# icsp.net
KiCad netlist of a schematic drawn in EAGLE
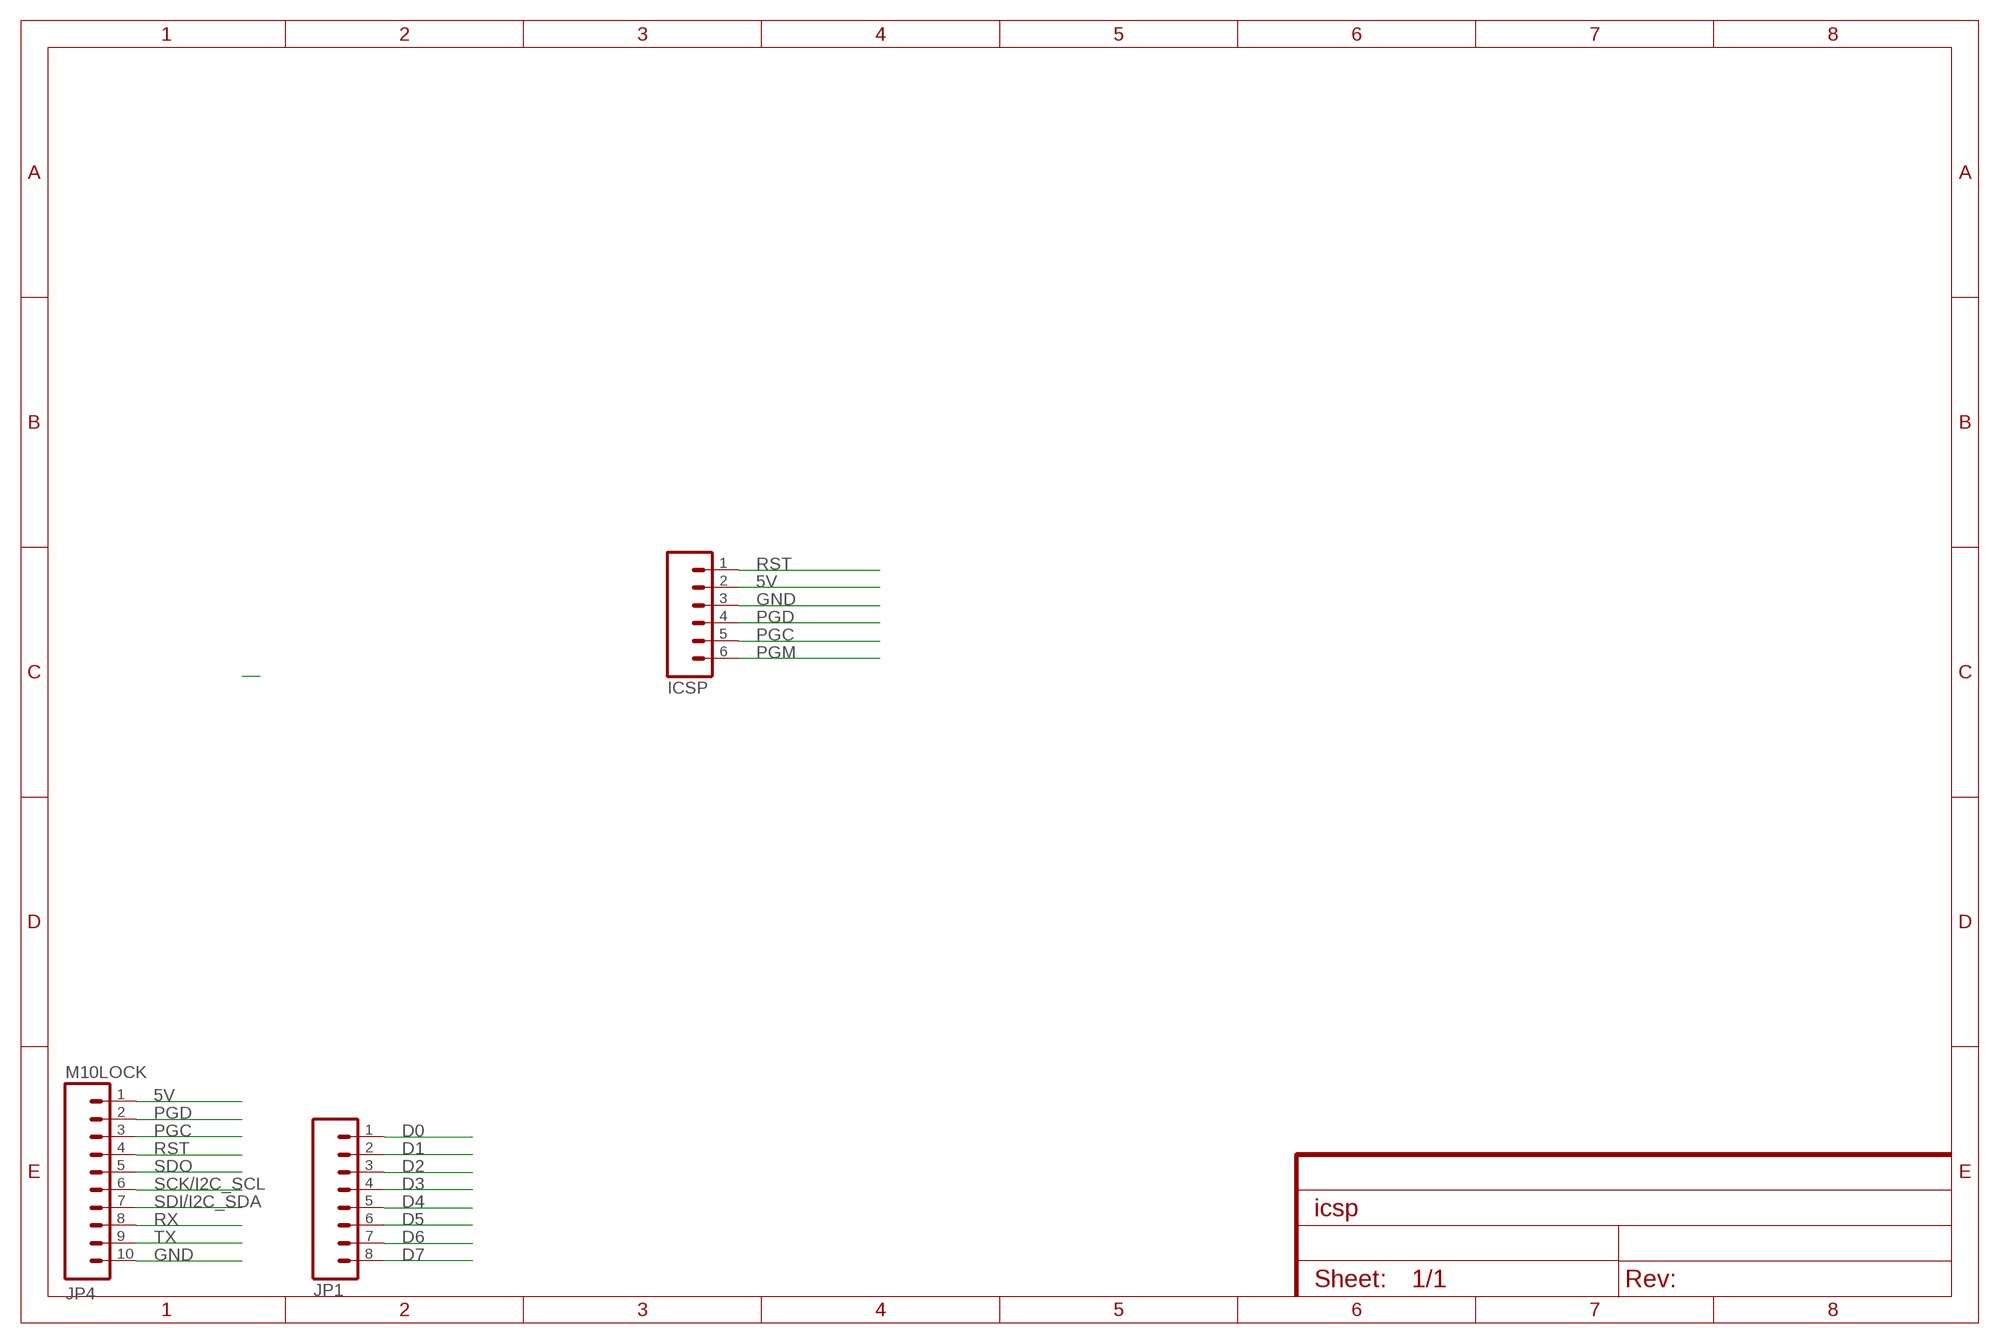
[diagram p0: schematic, sheet 1]

(export (version "E")
  (design (tool "Eeschema 10.0.6"))
  (components
    (comp (ref "ICSP")
      (value "M06LOCK")
      (footprint "eagle-import:1X06_LOCK")
      (libsource (lib "eagle-import") (part "M06LOCK"))
    )
    (comp (ref "JP1")
      (value "M08LOCK")
      (footprint "eagle-import:1X08_LOCK")
      (libsource (lib "eagle-import") (part "M08LOCK"))
    )
    (comp (ref "JP4")
      (value "M10LOCK")
      (footprint "eagle-import:1X10_LOCK")
      (libsource (lib "eagle-import") (part "M10LOCK"))
    )
  )
  (nets
    (net (code "1") (name "/5V") (class "Default")
      (node (ref "ICSP") (pin "2") (pinfunction "2_2") (pintype "passive"))
      (node (ref "JP4") (pin "1") (pinfunction "1_1") (pintype "passive"))
    )
    (net (code "2") (name "/D0") (class "Default")
      (node (ref "JP1") (pin "1") (pinfunction "1_1") (pintype "passive"))
    )
    (net (code "3") (name "/D1") (class "Default")
      (node (ref "JP1") (pin "2") (pinfunction "2_2") (pintype "passive"))
    )
    (net (code "4") (name "/D2") (class "Default")
      (node (ref "JP1") (pin "3") (pinfunction "3_3") (pintype "passive"))
    )
    (net (code "5") (name "/D3") (class "Default")
      (node (ref "JP1") (pin "4") (pinfunction "4_4") (pintype "passive"))
    )
    (net (code "6") (name "/D4") (class "Default")
      (node (ref "JP1") (pin "5") (pinfunction "5_5") (pintype "passive"))
    )
    (net (code "7") (name "/D5") (class "Default")
      (node (ref "JP1") (pin "6") (pinfunction "6_6") (pintype "passive"))
    )
    (net (code "8") (name "/D6") (class "Default")
      (node (ref "JP1") (pin "7") (pinfunction "7_7") (pintype "passive"))
    )
    (net (code "9") (name "/D7") (class "Default")
      (node (ref "JP1") (pin "8") (pinfunction "8_8") (pintype "passive"))
    )
    (net (code "10") (name "/GND") (class "Default")
      (node (ref "ICSP") (pin "3") (pinfunction "3_3") (pintype "passive"))
      (node (ref "JP4") (pin "10") (pinfunction "10_10") (pintype "passive"))
    )
    (net (code "11") (name "/PGC") (class "Default")
      (node (ref "ICSP") (pin "5") (pinfunction "5_5") (pintype "passive"))
      (node (ref "JP4") (pin "3") (pinfunction "3_3") (pintype "passive"))
    )
    (net (code "12") (name "/PGD") (class "Default")
      (node (ref "ICSP") (pin "4") (pinfunction "4_4") (pintype "passive"))
      (node (ref "JP4") (pin "2") (pinfunction "2_2") (pintype "passive"))
    )
    (net (code "13") (name "/PGM") (class "Default")
      (node (ref "ICSP") (pin "6") (pinfunction "6_6") (pintype "passive"))
    )
    (net (code "14") (name "/RST") (class "Default")
      (node (ref "ICSP") (pin "1") (pinfunction "1_1") (pintype "passive"))
      (node (ref "JP4") (pin "4") (pinfunction "4_4") (pintype "passive"))
    )
    (net (code "15") (name "/RX") (class "Default")
      (node (ref "JP4") (pin "8") (pinfunction "8_8") (pintype "passive"))
    )
    (net (code "16") (name "/SCK{slash}I2C_SCL") (class "Default")
      (node (ref "JP4") (pin "6") (pinfunction "6_6") (pintype "passive"))
    )
    (net (code "17") (name "/SDI{slash}I2C_SDA") (class "Default")
      (node (ref "JP4") (pin "7") (pinfunction "7_7") (pintype "passive"))
    )
    (net (code "18") (name "/SDO") (class "Default")
      (node (ref "JP4") (pin "5") (pinfunction "5_5") (pintype "passive"))
    )
    (net (code "19") (name "/TX") (class "Default")
      (node (ref "JP4") (pin "9") (pinfunction "9_9") (pintype "passive"))
    )
  )
)
